# CAN.net
KiCad netlist of a schematic drawn in Altium Designer
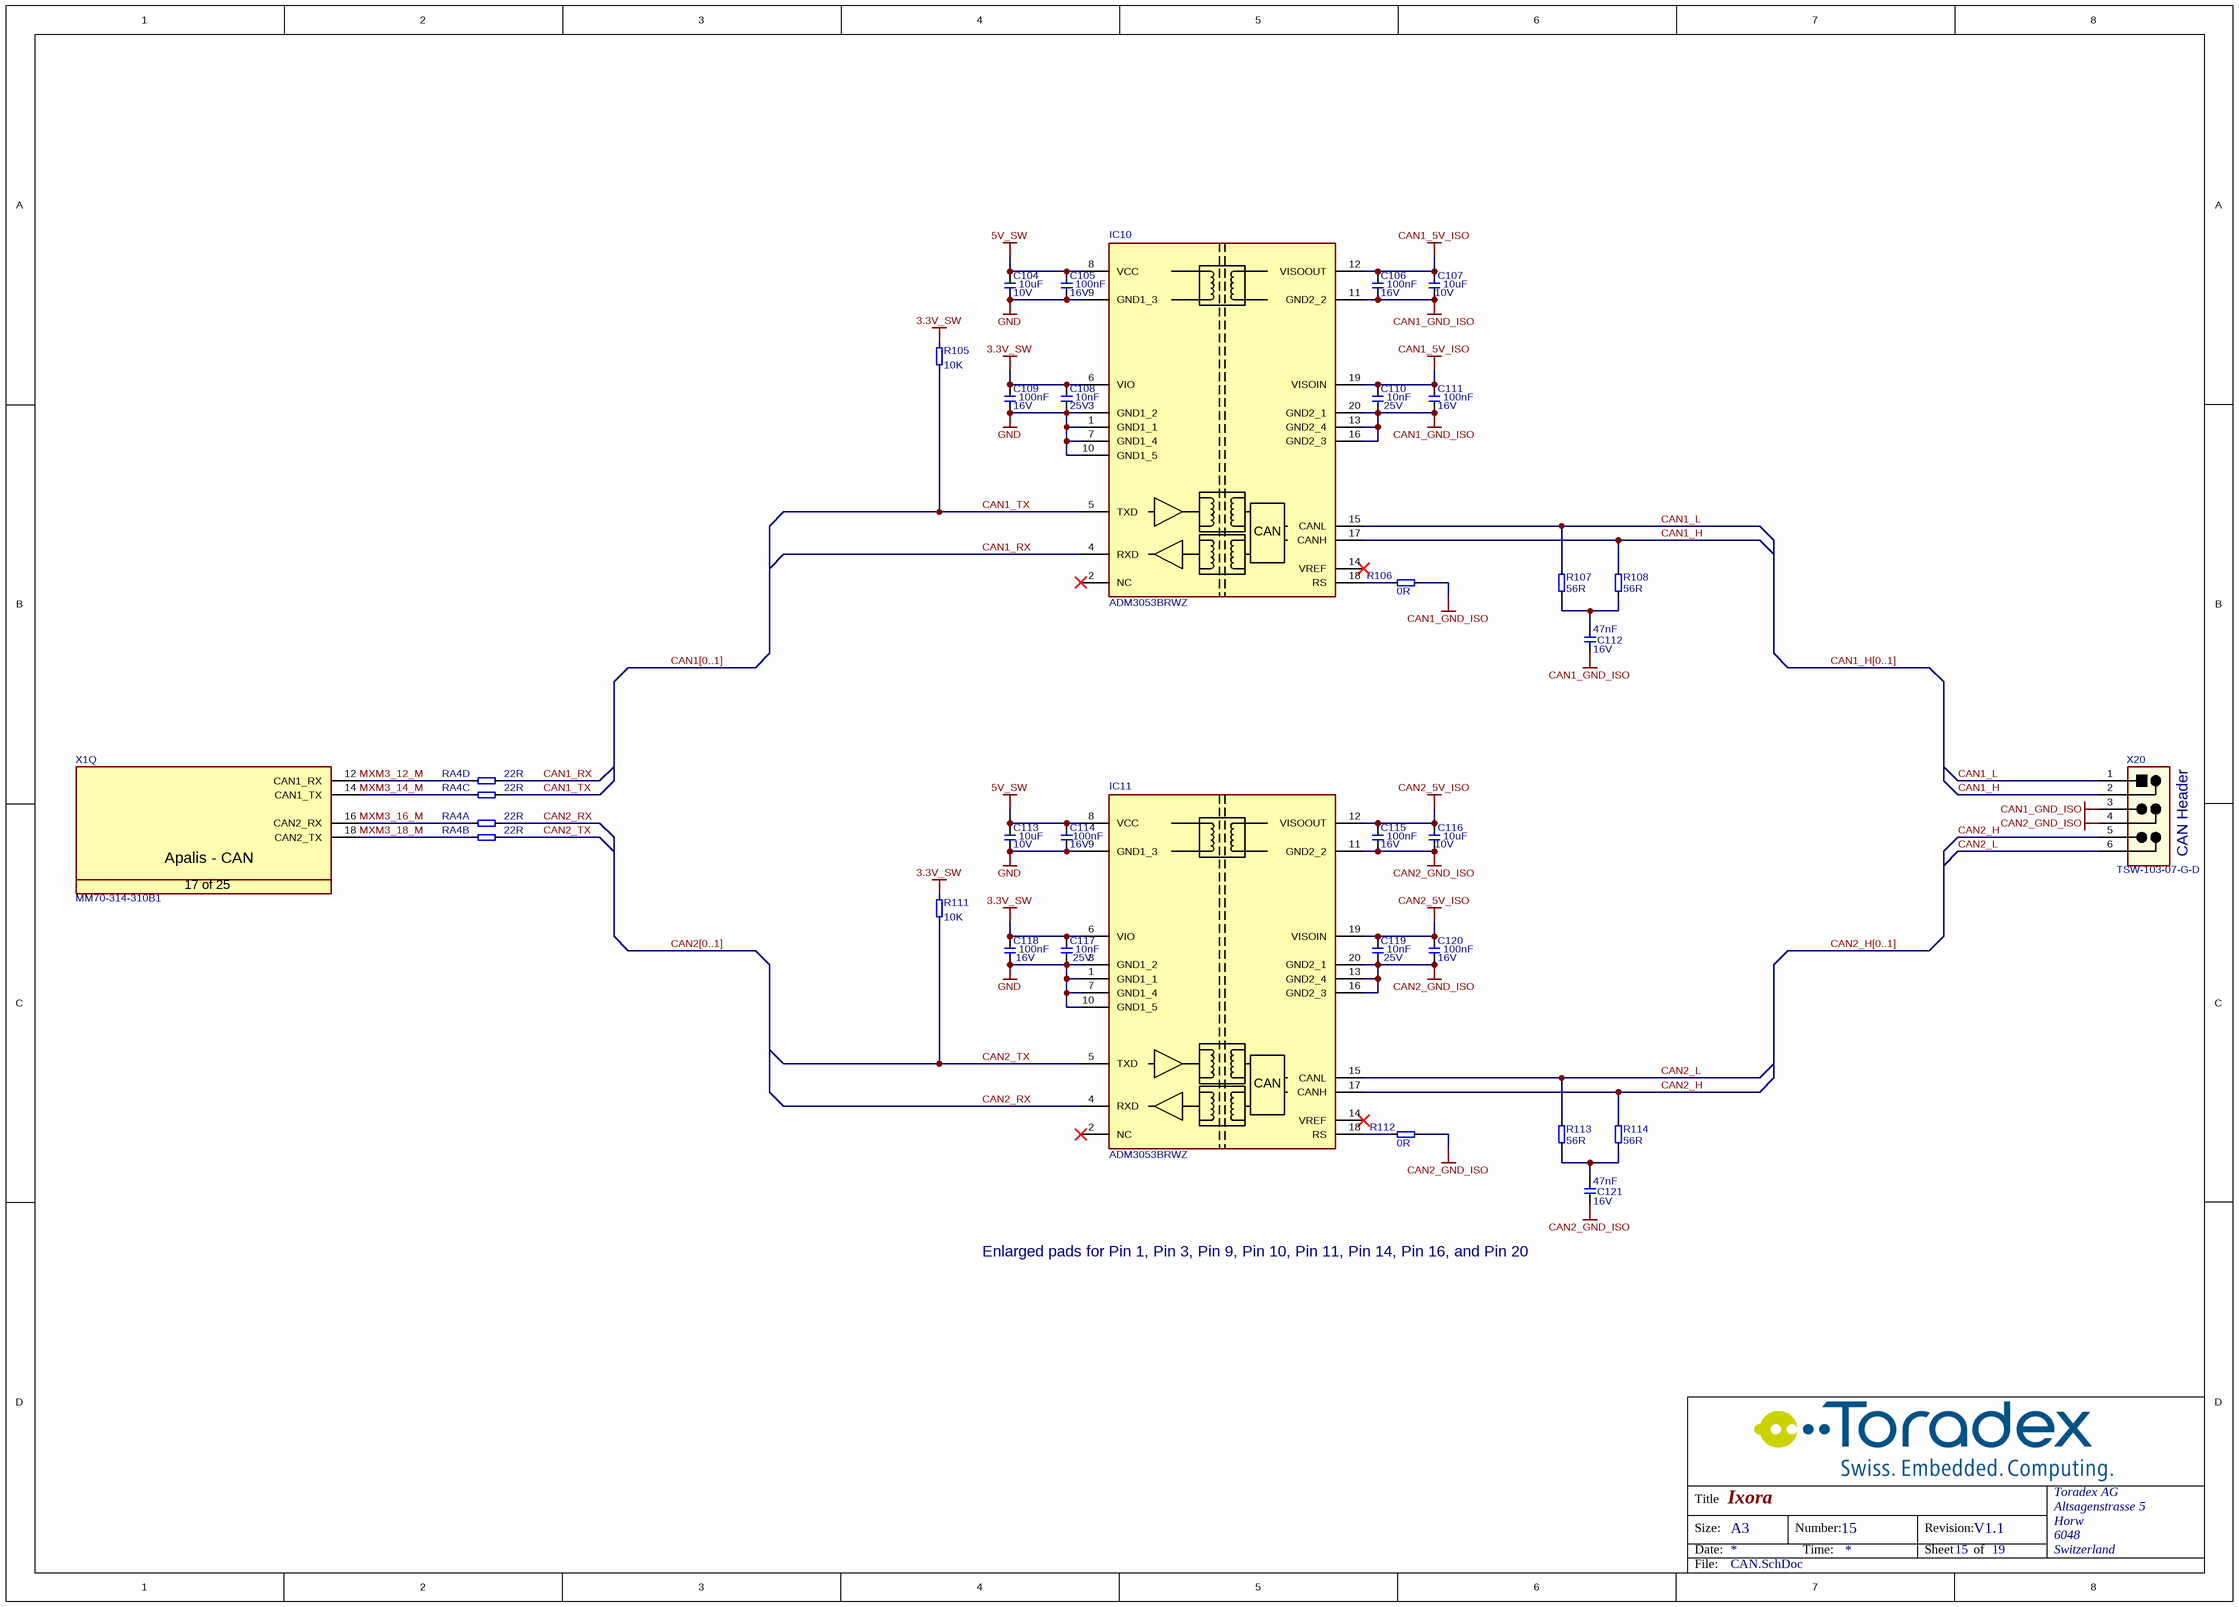
[diagram p0: CAN.SchDoc]

(export (version "E")
  (design (tool "Eeschema 10.0.6"))
  (components
    (comp (ref "C104")
      (value "10uF")
      (footprint "T_CAPC0603X33N")
      (description "Capacitor Ceramic X5R 10uF 10V 20% 0603")
      (fields (field (name "TOLERANCE") "20%") (field (name "RATING") "10V"))
      (libsource (lib "Ixora") (part "C-X5R-10uF-10V-20%-0603"))
    )
    (comp (ref "C105")
      (value "100nF")
      (footprint "CAPC1005X60N")
      (description "Capacitor Ceramic X7R 100nF 16V 10% 0402")
      (fields (field (name "TOLERANCE") "10%") (field (name "RATING") "16V"))
      (libsource (lib "Ixora") (part "C-X7R-100nF-16V-10%-0402"))
    )
    (comp (ref "C106")
      (value "100nF")
      (footprint "CAPC1005X60N")
      (description "Capacitor Ceramic X7R 100nF 16V 10% 0402")
      (fields (field (name "TOLERANCE") "10%") (field (name "RATING") "16V"))
      (libsource (lib "Ixora") (part "C-X7R-100nF-16V-10%-0402"))
    )
    (comp (ref "C107")
      (value "10uF")
      (footprint "T_CAPC0603X33N")
      (description "Capacitor Ceramic X5R 10uF 10V 20% 0603")
      (fields (field (name "TOLERANCE") "20%") (field (name "RATING") "10V"))
      (libsource (lib "Ixora") (part "C-X5R-10uF-10V-20%-0603"))
    )
    (comp (ref "C108")
      (value "10nF")
      (footprint "CAPC1005X60N")
      (description "Capacitor Ceramic X7R 10nF 25V 10% 0402")
      (fields (field (name "TOLERANCE") "10%") (field (name "RATING") "25V"))
      (libsource (lib "Ixora") (part "C-X7R-10nF-25V-10%-0402"))
    )
    (comp (ref "C109")
      (value "100nF")
      (footprint "CAPC1005X60N")
      (description "Capacitor Ceramic X7R 100nF 16V 10% 0402")
      (fields (field (name "TOLERANCE") "10%") (field (name "RATING") "16V"))
      (libsource (lib "Ixora") (part "C-X7R-100nF-16V-10%-0402"))
    )
    (comp (ref "C110")
      (value "10nF")
      (footprint "CAPC1005X60N")
      (description "Capacitor Ceramic X7R 10nF 25V 10% 0402")
      (fields (field (name "TOLERANCE") "10%") (field (name "RATING") "25V"))
      (libsource (lib "Ixora") (part "C-X7R-10nF-25V-10%-0402"))
    )
    (comp (ref "C111")
      (value "100nF")
      (footprint "CAPC1005X60N")
      (description "Capacitor Ceramic X7R 100nF 16V 10% 0402")
      (fields (field (name "TOLERANCE") "10%") (field (name "RATING") "16V"))
      (libsource (lib "Ixora") (part "C-X7R-100nF-16V-10%-0402"))
    )
    (comp (ref "C112")
      (value "47nF")
      (footprint "T_CAPC0603X33N")
      (description "Capacitor Ceramic X7R 47nF 16V 10% 0603")
      (fields (field (name "TOLERANCE") "10%") (field (name "RATING") "16V"))
      (libsource (lib "Ixora") (part "C-X7R-47nF-16V-10%-0603"))
    )
    (comp (ref "C113")
      (value "10uF")
      (footprint "T_CAPC0603X33N")
      (description "Capacitor Ceramic X5R 10uF 10V 20% 0603")
      (fields (field (name "TOLERANCE") "20%") (field (name "RATING") "10V"))
      (libsource (lib "Ixora") (part "C-X5R-10uF-10V-20%-0603"))
    )
    (comp (ref "C114")
      (value "100nF")
      (footprint "CAPC1005X60N")
      (description "Capacitor Ceramic X7R 100nF 16V 10% 0402")
      (fields (field (name "TOLERANCE") "10%") (field (name "RATING") "16V"))
      (libsource (lib "Ixora") (part "C-X7R-100nF-16V-10%-0402"))
    )
    (comp (ref "C115")
      (value "100nF")
      (footprint "CAPC1005X60N")
      (description "Capacitor Ceramic X7R 100nF 16V 10% 0402")
      (fields (field (name "TOLERANCE") "10%") (field (name "RATING") "16V"))
      (libsource (lib "Ixora") (part "C-X7R-100nF-16V-10%-0402"))
    )
    (comp (ref "C116")
      (value "10uF")
      (footprint "T_CAPC0603X33N")
      (description "Capacitor Ceramic X5R 10uF 10V 20% 0603")
      (fields (field (name "TOLERANCE") "20%") (field (name "RATING") "10V"))
      (libsource (lib "Ixora") (part "C-X5R-10uF-10V-20%-0603"))
    )
    (comp (ref "C117")
      (value "10nF")
      (footprint "CAPC1005X60N")
      (description "Capacitor Ceramic X7R 10nF 25V 10% 0402")
      (fields (field (name "TOLERANCE") "10%") (field (name "RATING") "25V"))
      (libsource (lib "Ixora") (part "C-X7R-10nF-25V-10%-0402"))
    )
    (comp (ref "C118")
      (value "100nF")
      (footprint "CAPC1005X60N")
      (description "Capacitor Ceramic X7R 100nF 16V 10% 0402")
      (fields (field (name "TOLERANCE") "10%") (field (name "RATING") "16V"))
      (libsource (lib "Ixora") (part "C-X7R-100nF-16V-10%-0402"))
    )
    (comp (ref "C119")
      (value "10nF")
      (footprint "CAPC1005X60N")
      (description "Capacitor Ceramic X7R 10nF 25V 10% 0402")
      (fields (field (name "TOLERANCE") "10%") (field (name "RATING") "25V"))
      (libsource (lib "Ixora") (part "C-X7R-10nF-25V-10%-0402"))
    )
    (comp (ref "C120")
      (value "100nF")
      (footprint "CAPC1005X60N")
      (description "Capacitor Ceramic X7R 100nF 16V 10% 0402")
      (fields (field (name "TOLERANCE") "10%") (field (name "RATING") "16V"))
      (libsource (lib "Ixora") (part "C-X7R-100nF-16V-10%-0402"))
    )
    (comp (ref "C121")
      (value "47nF")
      (footprint "T_CAPC0603X33N")
      (description "Capacitor Ceramic X7R 47nF 16V 10% 0603")
      (fields (field (name "TOLERANCE") "10%") (field (name "RATING") "16V"))
      (libsource (lib "Ixora") (part "C-X7R-47nF-16V-10%-0603"))
    )
    (comp (ref "IC10")
      (value "ADM3053BRWZ")
      (footprint "T_AD_ADM3053")
      (description "Signal and Power Isolated CAN Transceiver  with Integrated Isolated DC-to-DC Converter")
      (fields (field (name "MANUFACTURER PART NO.") "ADM3053BRWZ"))
      (libsource (lib "Ixora") (part "IC-AD-ADM3053BRWZ"))
    )
    (comp (ref "IC11")
      (value "ADM3053BRWZ")
      (footprint "T_AD_ADM3053")
      (description "Signal and Power Isolated CAN Transceiver  with Integrated Isolated DC-to-DC Converter")
      (fields (field (name "MANUFACTURER PART NO.") "ADM3053BRWZ"))
      (libsource (lib "Ixora") (part "IC-AD-ADM3053BRWZ"))
    )
    (comp (ref "R105")
      (value "10K")
      (footprint "RESC1005X40N")
      (description "Resistor 10 Kohm 63mW 5% 0402")
      (fields (field (name "TOLERANCE") "5%"))
      (libsource (lib "Ixora") (part "R-10KR-63mW-5%-0402"))
    )
    (comp (ref "R106")
      (value "0R")
      (footprint "RESC1005X40N")
      (description "Resistor 0 ohm 63mW 1% 0402")
      (fields (field (name "TOLERANCE") "1%"))
      (libsource (lib "Ixora") (part "R-0R-63mW-1%-0402"))
    )
    (comp (ref "R107")
      (value "56R")
      (footprint "T_RESC0603X30N")
      (description "Resistor 56 ohm 63mW 5% 0603")
      (fields (field (name "TOLERANCE") "5%"))
      (libsource (lib "Ixora") (part "R-56R-63mW-5%-0603"))
    )
    (comp (ref "R108")
      (value "56R")
      (footprint "T_RESC0603X30N")
      (description "Resistor 56 ohm 63mW 5% 0603")
      (fields (field (name "TOLERANCE") "5%"))
      (libsource (lib "Ixora") (part "R-56R-63mW-5%-0603"))
    )
    (comp (ref "R111")
      (value "10K")
      (footprint "RESC1005X40N")
      (description "Resistor 10 Kohm 63mW 5% 0402")
      (fields (field (name "TOLERANCE") "5%"))
      (libsource (lib "Ixora") (part "R-10KR-63mW-5%-0402"))
    )
    (comp (ref "R112")
      (value "0R")
      (footprint "RESC1005X40N")
      (description "Resistor 0 ohm 63mW 1% 0402")
      (fields (field (name "TOLERANCE") "1%"))
      (libsource (lib "Ixora") (part "R-0R-63mW-1%-0402"))
    )
    (comp (ref "R113")
      (value "56R")
      (footprint "T_RESC0603X30N")
      (description "Resistor 56 ohm 63mW 5% 0603")
      (fields (field (name "TOLERANCE") "5%"))
      (libsource (lib "Ixora") (part "R-56R-63mW-5%-0603"))
    )
    (comp (ref "R114")
      (value "56R")
      (footprint "T_RESC0603X30N")
      (description "Resistor 56 ohm 63mW 5% 0603")
      (fields (field (name "TOLERANCE") "5%"))
      (libsource (lib "Ixora") (part "R-56R-63mW-5%-0603"))
    )
    (comp (ref "RA4")
      (value "22R")
      (footprint "T_Resistor_Array_X4")
      (description "Resistor Array 22 R 63mW 5% 1206")
      (fields (field (name "TOLERANCE") "5%"))
      (libsource (lib "Ixora") (part "RA-22R-63mW-5%-1206-div"))
    )
    (comp (ref "X1")
      (value "CON-JAE-MM70-314-310B1-314-0.5mm")
      (footprint "T_JAE_MM70-314-310B1")
      (description "MXM3 Connector")
      (fields (field (name "MANUFACTURER PART NO.") "MM70-314-310B1"))
      (libsource (lib "Ixora") (part "CON-JAE-MM70-314-310B1-314-0.5mm"))
    )
    (comp (ref "X20")
      (value "TSW-103-07-G-D")
      (footprint "T_Samtec_TSW-103-07-G-D")
      (description "Header Male, 2x3 Pins, 2.54mm pitch")
      (fields (field (name "MANUFACTURER PART NO.") "TSW-103-07-G-D"))
      (libsource (lib "Ixora") (part "CON-Samtec-TSW-103-07-G-D"))
    )
  )
  (nets
    (net (code "10") (name "/CAN1_H") (class "Default")
      (node (ref "IC10") (pin "17") (pinfunction "CANH_17") (pintype "passive"))
      (node (ref "R108") (pin "2") (pinfunction "2_2") (pintype "passive"))
      (node (ref "X20") (pin "2") (pinfunction "2_2") (pintype "passive"))
    )
    (net (code "12") (name "/CAN1_L") (class "Default")
      (node (ref "IC10") (pin "15") (pinfunction "CANL_15") (pintype "passive"))
      (node (ref "R107") (pin "2") (pinfunction "2_2") (pintype "passive"))
      (node (ref "X20") (pin "1") (pinfunction "1_1") (pintype "passive"))
    )
    (net (code "13") (name "/CAN1_RX") (class "Default")
      (node (ref "IC10") (pin "4") (pinfunction "RXD_4") (pintype "passive"))
      (node (ref "RA4") (pin "8") (pinfunction "8_8") (pintype "passive"))
    )
    (net (code "14") (name "/CAN1_TX") (class "Default")
      (node (ref "IC10") (pin "5") (pinfunction "TXD_5") (pintype "passive"))
      (node (ref "R105") (pin "1") (pinfunction "1_1") (pintype "passive"))
      (node (ref "RA4") (pin "7") (pinfunction "7_7") (pintype "passive"))
    )
    (net (code "16") (name "/CAN2_H") (class "Default")
      (node (ref "IC11") (pin "17") (pinfunction "CANH_17") (pintype "passive"))
      (node (ref "R114") (pin "2") (pinfunction "2_2") (pintype "passive"))
      (node (ref "X20") (pin "5") (pinfunction "5_5") (pintype "passive"))
    )
    (net (code "18") (name "/CAN2_L") (class "Default")
      (node (ref "IC11") (pin "15") (pinfunction "CANL_15") (pintype "passive"))
      (node (ref "R113") (pin "2") (pinfunction "2_2") (pintype "passive"))
      (node (ref "X20") (pin "6") (pinfunction "6_6") (pintype "passive"))
    )
    (net (code "19") (name "/CAN2_RX") (class "Default")
      (node (ref "IC11") (pin "4") (pinfunction "RXD_4") (pintype "passive"))
      (node (ref "RA4") (pin "5") (pinfunction "5_5") (pintype "passive"))
    )
    (net (code "20") (name "/CAN2_TX") (class "Default")
      (node (ref "IC11") (pin "5") (pinfunction "TXD_5") (pintype "passive"))
      (node (ref "R111") (pin "1") (pinfunction "1_1") (pintype "passive"))
      (node (ref "RA4") (pin "6") (pinfunction "6_6") (pintype "passive"))
    )
    (net (code "21") (name "/MXM3_12_M") (class "Default")
      (node (ref "RA4") (pin "4") (pinfunction "4_4") (pintype "passive"))
      (node (ref "X1") (pin "12") (pinfunction "CAN1_RX_12") (pintype "passive"))
    )
    (net (code "22") (name "/MXM3_14_M") (class "Default")
      (node (ref "RA4") (pin "3") (pinfunction "3_3") (pintype "passive"))
      (node (ref "X1") (pin "14") (pinfunction "CAN1_TX_14") (pintype "passive"))
    )
    (net (code "23") (name "/MXM3_16_M") (class "Default")
      (node (ref "RA4") (pin "1") (pinfunction "1_1") (pintype "passive"))
      (node (ref "X1") (pin "16") (pinfunction "CAN2_RX_16") (pintype "passive"))
    )
    (net (code "24") (name "/MXM3_18_M") (class "Default")
      (node (ref "RA4") (pin "2") (pinfunction "2_2") (pintype "passive"))
      (node (ref "X1") (pin "18") (pinfunction "CAN2_TX_18") (pintype "passive"))
    )
    (net (code "25") (name "3.3V_SW") (class "Default")
      (node (ref "C108") (pin "2") (pinfunction "2_2") (pintype "passive"))
      (node (ref "C109") (pin "2") (pinfunction "2_2") (pintype "passive"))
      (node (ref "C117") (pin "2") (pinfunction "2_2") (pintype "passive"))
      (node (ref "C118") (pin "2") (pinfunction "2_2") (pintype "passive"))
      (node (ref "IC10") (pin "6") (pinfunction "VIO_6") (pintype "passive"))
      (node (ref "IC11") (pin "6") (pinfunction "VIO_6") (pintype "passive"))
      (node (ref "R105") (pin "2") (pinfunction "2_2") (pintype "passive"))
      (node (ref "R111") (pin "2") (pinfunction "2_2") (pintype "passive"))
    )
    (net (code "26") (name "5V_SW") (class "Default")
      (node (ref "C104") (pin "2") (pinfunction "2_2") (pintype "passive"))
      (node (ref "C105") (pin "2") (pinfunction "2_2") (pintype "passive"))
      (node (ref "C113") (pin "2") (pinfunction "2_2") (pintype "passive"))
      (node (ref "C114") (pin "2") (pinfunction "2_2") (pintype "passive"))
      (node (ref "IC10") (pin "8") (pinfunction "VCC_8") (pintype "passive"))
      (node (ref "IC11") (pin "8") (pinfunction "VCC_8") (pintype "passive"))
    )
    (net (code "27") (name "CAN1_5V_ISO") (class "Default")
      (node (ref "C106") (pin "2") (pinfunction "2_2") (pintype "passive"))
      (node (ref "C107") (pin "2") (pinfunction "2_2") (pintype "passive"))
      (node (ref "C110") (pin "2") (pinfunction "2_2") (pintype "passive"))
      (node (ref "C111") (pin "2") (pinfunction "2_2") (pintype "passive"))
      (node (ref "IC10") (pin "12") (pinfunction "VISOOUT_12") (pintype "passive"))
      (node (ref "IC10") (pin "19") (pinfunction "VISOIN_19") (pintype "passive"))
    )
    (net (code "28") (name "CAN1_GND_ISO") (class "Default")
      (node (ref "C106") (pin "1") (pinfunction "1_1") (pintype "passive"))
      (node (ref "C107") (pin "1") (pinfunction "1_1") (pintype "passive"))
      (node (ref "C110") (pin "1") (pinfunction "1_1") (pintype "passive"))
      (node (ref "C111") (pin "1") (pinfunction "1_1") (pintype "passive"))
      (node (ref "C112") (pin "1") (pinfunction "1_1") (pintype "passive"))
      (node (ref "IC10") (pin "11") (pinfunction "GND2_2_11") (pintype "passive"))
      (node (ref "IC10") (pin "13") (pinfunction "GND2_4_13") (pintype "passive"))
      (node (ref "IC10") (pin "16") (pinfunction "GND2_3_16") (pintype "passive"))
      (node (ref "IC10") (pin "20") (pinfunction "GND2_1_20") (pintype "passive"))
      (node (ref "R106") (pin "1") (pinfunction "1_1") (pintype "passive"))
      (node (ref "X20") (pin "3") (pinfunction "3_3") (pintype "passive"))
    )
    (net (code "29") (name "CAN2_5V_ISO") (class "Default")
      (node (ref "C115") (pin "2") (pinfunction "2_2") (pintype "passive"))
      (node (ref "C116") (pin "2") (pinfunction "2_2") (pintype "passive"))
      (node (ref "C119") (pin "2") (pinfunction "2_2") (pintype "passive"))
      (node (ref "C120") (pin "2") (pinfunction "2_2") (pintype "passive"))
      (node (ref "IC11") (pin "12") (pinfunction "VISOOUT_12") (pintype "passive"))
      (node (ref "IC11") (pin "19") (pinfunction "VISOIN_19") (pintype "passive"))
    )
    (net (code "30") (name "CAN2_GND_ISO") (class "Default")
      (node (ref "C115") (pin "1") (pinfunction "1_1") (pintype "passive"))
      (node (ref "C116") (pin "1") (pinfunction "1_1") (pintype "passive"))
      (node (ref "C119") (pin "1") (pinfunction "1_1") (pintype "passive"))
      (node (ref "C120") (pin "1") (pinfunction "1_1") (pintype "passive"))
      (node (ref "C121") (pin "1") (pinfunction "1_1") (pintype "passive"))
      (node (ref "IC11") (pin "11") (pinfunction "GND2_2_11") (pintype "passive"))
      (node (ref "IC11") (pin "13") (pinfunction "GND2_4_13") (pintype "passive"))
      (node (ref "IC11") (pin "16") (pinfunction "GND2_3_16") (pintype "passive"))
      (node (ref "IC11") (pin "20") (pinfunction "GND2_1_20") (pintype "passive"))
      (node (ref "R112") (pin "1") (pinfunction "1_1") (pintype "passive"))
      (node (ref "X20") (pin "4") (pinfunction "4_4") (pintype "passive"))
    )
    (net (code "31") (name "GND") (class "Default")
      (node (ref "C104") (pin "1") (pinfunction "1_1") (pintype "passive"))
      (node (ref "C105") (pin "1") (pinfunction "1_1") (pintype "passive"))
      (node (ref "C108") (pin "1") (pinfunction "1_1") (pintype "passive"))
      (node (ref "C109") (pin "1") (pinfunction "1_1") (pintype "passive"))
      (node (ref "C113") (pin "1") (pinfunction "1_1") (pintype "passive"))
      (node (ref "C114") (pin "1") (pinfunction "1_1") (pintype "passive"))
      (node (ref "C117") (pin "1") (pinfunction "1_1") (pintype "passive"))
      (node (ref "C118") (pin "1") (pinfunction "1_1") (pintype "passive"))
      (node (ref "IC10") (pin "1") (pinfunction "GND1_1_1") (pintype "passive"))
      (node (ref "IC10") (pin "10") (pinfunction "GND1_5_10") (pintype "passive"))
      (node (ref "IC10") (pin "3") (pinfunction "GND1_2_3") (pintype "passive"))
      (node (ref "IC10") (pin "7") (pinfunction "GND1_4_7") (pintype "passive"))
      (node (ref "IC10") (pin "9") (pinfunction "GND1_3_9") (pintype "passive"))
      (node (ref "IC11") (pin "1") (pinfunction "GND1_1_1") (pintype "passive"))
      (node (ref "IC11") (pin "10") (pinfunction "GND1_5_10") (pintype "passive"))
      (node (ref "IC11") (pin "3") (pinfunction "GND1_2_3") (pintype "passive"))
      (node (ref "IC11") (pin "7") (pinfunction "GND1_4_7") (pintype "passive"))
      (node (ref "IC11") (pin "9") (pinfunction "GND1_3_9") (pintype "passive"))
    )
    (net (code "32") (name "Net-(C112-Pad2)") (class "Default")
      (node (ref "C112") (pin "2") (pinfunction "2_2") (pintype "passive"))
      (node (ref "R107") (pin "1") (pinfunction "1_1") (pintype "passive"))
      (node (ref "R108") (pin "1") (pinfunction "1_1") (pintype "passive"))
    )
    (net (code "33") (name "Net-(C121-Pad2)") (class "Default")
      (node (ref "C121") (pin "2") (pinfunction "2_2") (pintype "passive"))
      (node (ref "R113") (pin "1") (pinfunction "1_1") (pintype "passive"))
      (node (ref "R114") (pin "1") (pinfunction "1_1") (pintype "passive"))
    )
    (net (code "34") (name "Net-(IC10-RS)") (class "Default")
      (node (ref "IC10") (pin "18") (pinfunction "RS_18") (pintype "passive"))
      (node (ref "R106") (pin "2") (pinfunction "2_2") (pintype "passive"))
    )
    (net (code "35") (name "Net-(IC11-RS)") (class "Default")
      (node (ref "IC11") (pin "18") (pinfunction "RS_18") (pintype "passive"))
      (node (ref "R112") (pin "2") (pinfunction "2_2") (pintype "passive"))
    )
    (net (code "36") (name "unconnected-(IC10-NC-Pad2)") (class "Default")
      (node (ref "IC10") (pin "2") (pinfunction "NC_2") (pintype "passive+no_connect"))
    )
    (net (code "37") (name "unconnected-(IC10-VREF-Pad14)") (class "Default")
      (node (ref "IC10") (pin "14") (pinfunction "VREF_14") (pintype "passive+no_connect"))
    )
    (net (code "38") (name "unconnected-(IC11-NC-Pad2)") (class "Default")
      (node (ref "IC11") (pin "2") (pinfunction "NC_2") (pintype "passive+no_connect"))
    )
    (net (code "39") (name "unconnected-(IC11-VREF-Pad14)") (class "Default")
      (node (ref "IC11") (pin "14") (pinfunction "VREF_14") (pintype "passive+no_connect"))
    )
  )
)
